# ft232.net
KiCad netlist of a schematic drawn in EAGLE
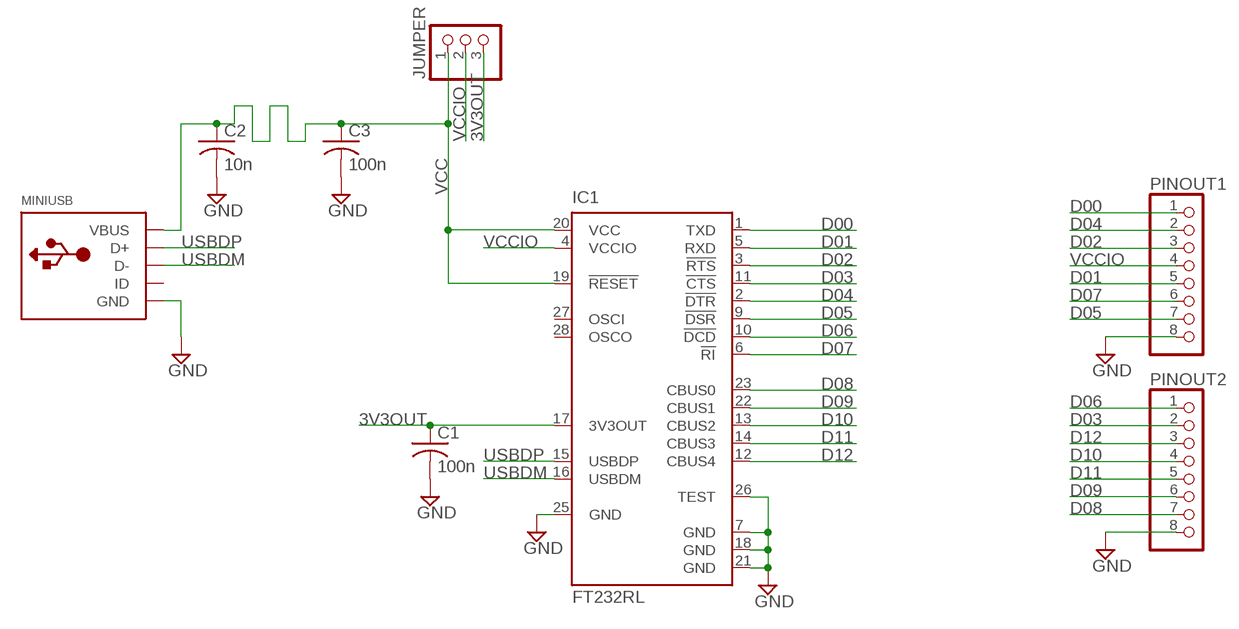
[diagram p0: schematic, sheet 1]

(export (version "E")
  (design (tool "Eeschema 10.0.6"))
  (components
    (comp (ref "C1")
      (value "100n")
      (footprint "eagle-import:C0805")
      (libsource (lib "eagle-import") (part "C-USC0805"))
    )
    (comp (ref "C2")
      (value "10n")
      (footprint "eagle-import:C0805")
      (libsource (lib "eagle-import") (part "C-USC0805"))
    )
    (comp (ref "C3")
      (value "100n")
      (footprint "eagle-import:C0805")
      (libsource (lib "eagle-import") (part "C-USC0805"))
    )
    (comp (ref "IC1")
      (value "FT232RL")
      (footprint "eagle-import:SSOP28")
      (libsource (lib "eagle-import") (part "FT232RL"))
    )
    (comp (ref "JUMPER")
      (value "PINHD-1X3CB")
      (footprint "eagle-import:1X03-CLEANBIG")
      (libsource (lib "eagle-import") (part "PINHD-1X3CB"))
    )
    (comp (ref "MINIUSB")
      (value "USBMINIB")
      (footprint "eagle-import:USB-MINIB")
      (libsource (lib "eagle-import") (part "USBMINIB"))
    )
    (comp (ref "PINOUT1")
      (value "PINHD-1X8")
      (footprint "eagle-import:1X08")
      (libsource (lib "eagle-import") (part "PINHD-1X8"))
    )
    (comp (ref "PINOUT2")
      (value "PINHD-1X8")
      (footprint "eagle-import:1X08")
      (libsource (lib "eagle-import") (part "PINHD-1X8"))
    )
  )
  (nets
    (net (code "1") (name "/3V3OUT") (class "Default")
      (node (ref "C1") (pin "1") (pinfunction "1_1") (pintype "passive"))
      (node (ref "IC1") (pin "17") (pinfunction "3V3OUT_17") (pintype "output"))
      (node (ref "JUMPER") (pin "3") (pinfunction "3_3") (pintype "passive"))
    )
    (net (code "2") (name "/D00") (class "Default")
      (node (ref "IC1") (pin "1") (pinfunction "TXD_1") (pintype "output"))
      (node (ref "PINOUT1") (pin "1") (pinfunction "1_1") (pintype "passive"))
    )
    (net (code "3") (name "/D01") (class "Default")
      (node (ref "IC1") (pin "5") (pinfunction "RXD_5") (pintype "input"))
      (node (ref "PINOUT1") (pin "5") (pinfunction "5_5") (pintype "passive"))
    )
    (net (code "4") (name "/D02") (class "Default")
      (node (ref "IC1") (pin "3") (pinfunction "~{RTS}_3") (pintype "output"))
      (node (ref "PINOUT1") (pin "3") (pinfunction "3_3") (pintype "passive"))
    )
    (net (code "5") (name "/D03") (class "Default")
      (node (ref "IC1") (pin "11") (pinfunction "~{CTS}_11") (pintype "input"))
      (node (ref "PINOUT2") (pin "2") (pinfunction "2_2") (pintype "passive"))
    )
    (net (code "6") (name "/D04") (class "Default")
      (node (ref "IC1") (pin "2") (pinfunction "~{DTR}_2") (pintype "output"))
      (node (ref "PINOUT1") (pin "2") (pinfunction "2_2") (pintype "passive"))
    )
    (net (code "7") (name "/D05") (class "Default")
      (node (ref "IC1") (pin "9") (pinfunction "~{DSR}_9") (pintype "input"))
      (node (ref "PINOUT1") (pin "7") (pinfunction "7_7") (pintype "passive"))
    )
    (net (code "8") (name "/D06") (class "Default")
      (node (ref "IC1") (pin "10") (pinfunction "~{DCD}_10") (pintype "input"))
      (node (ref "PINOUT2") (pin "1") (pinfunction "1_1") (pintype "passive"))
    )
    (net (code "9") (name "/D07") (class "Default")
      (node (ref "IC1") (pin "6") (pinfunction "~{RI}_6") (pintype "input"))
      (node (ref "PINOUT1") (pin "6") (pinfunction "6_6") (pintype "passive"))
    )
    (net (code "10") (name "/D08") (class "Default")
      (node (ref "IC1") (pin "23") (pinfunction "CBUS0_23") (pintype "bidirectional"))
      (node (ref "PINOUT2") (pin "7") (pinfunction "7_7") (pintype "passive"))
    )
    (net (code "11") (name "/D09") (class "Default")
      (node (ref "IC1") (pin "22") (pinfunction "CBUS1_22") (pintype "bidirectional"))
      (node (ref "PINOUT2") (pin "6") (pinfunction "6_6") (pintype "passive"))
    )
    (net (code "12") (name "/D10") (class "Default")
      (node (ref "IC1") (pin "13") (pinfunction "CBUS2_13") (pintype "bidirectional"))
      (node (ref "PINOUT2") (pin "4") (pinfunction "4_4") (pintype "passive"))
    )
    (net (code "13") (name "/D11") (class "Default")
      (node (ref "IC1") (pin "14") (pinfunction "CBUS3_14") (pintype "bidirectional"))
      (node (ref "PINOUT2") (pin "5") (pinfunction "5_5") (pintype "passive"))
    )
    (net (code "14") (name "/D12") (class "Default")
      (node (ref "IC1") (pin "12") (pinfunction "CBUS4_12") (pintype "bidirectional"))
      (node (ref "PINOUT2") (pin "3") (pinfunction "3_3") (pintype "passive"))
    )
    (net (code "15") (name "/USBDM") (class "Default")
      (node (ref "IC1") (pin "16") (pinfunction "USBDM_16") (pintype "bidirectional"))
      (node (ref "MINIUSB") (pin "D-") (pinfunction "D-_D-") (pintype "bidirectional"))
    )
    (net (code "16") (name "/USBDP") (class "Default")
      (node (ref "IC1") (pin "15") (pinfunction "USBDP_15") (pintype "bidirectional"))
      (node (ref "MINIUSB") (pin "D+") (pinfunction "D+_D+") (pintype "bidirectional"))
    )
    (net (code "17") (name "/VCC") (class "Default")
      (node (ref "C2") (pin "1") (pinfunction "1_1") (pintype "passive"))
      (node (ref "C3") (pin "1") (pinfunction "1_1") (pintype "passive"))
      (node (ref "IC1") (pin "19") (pinfunction "~{RESET}_19") (pintype "input"))
      (node (ref "IC1") (pin "20") (pinfunction "VCC_20") (pintype "power_in"))
      (node (ref "JUMPER") (pin "1") (pinfunction "1_1") (pintype "passive"))
      (node (ref "MINIUSB") (pin "VBUS") (pinfunction "VBUS_VBUS") (pintype "power_in"))
    )
    (net (code "18") (name "/VCCIO") (class "Default")
      (node (ref "IC1") (pin "4") (pinfunction "VCCIO_4") (pintype "power_in"))
      (node (ref "JUMPER") (pin "2") (pinfunction "2_2") (pintype "passive"))
      (node (ref "PINOUT1") (pin "4") (pinfunction "4_4") (pintype "passive"))
    )
    (net (code "19") (name "GND") (class "Default")
      (node (ref "C1") (pin "2") (pinfunction "2_2") (pintype "passive"))
      (node (ref "C2") (pin "2") (pinfunction "2_2") (pintype "passive"))
      (node (ref "C3") (pin "2") (pinfunction "2_2") (pintype "passive"))
      (node (ref "IC1") (pin "18") (pinfunction "GND_18") (pintype "power_in"))
      (node (ref "IC1") (pin "21") (pinfunction "GND_21") (pintype "power_in"))
      (node (ref "IC1") (pin "25") (pinfunction "GND_25") (pintype "power_in"))
      (node (ref "IC1") (pin "26") (pinfunction "TEST_26") (pintype "input"))
      (node (ref "IC1") (pin "7") (pinfunction "GND_7") (pintype "power_in"))
      (node (ref "MINIUSB") (pin "GND") (pinfunction "GND_GND") (pintype "power_in"))
      (node (ref "PINOUT1") (pin "8") (pinfunction "8_8") (pintype "passive"))
      (node (ref "PINOUT2") (pin "8") (pinfunction "8_8") (pintype "passive"))
    )
    (net (code "20") (name "unconnected-(IC1-OSCI-Pad27)") (class "Default")
      (node (ref "IC1") (pin "27") (pinfunction "OSCI_27") (pintype "input"))
    )
    (net (code "21") (name "unconnected-(IC1-OSCO-Pad28)") (class "Default")
      (node (ref "IC1") (pin "28") (pinfunction "OSCO_28") (pintype "output"))
    )
    (net (code "22") (name "unconnected-(MINIUSB-PadID)") (class "Default")
      (node (ref "MINIUSB") (pin "ID") (pinfunction "ID_ID") (pintype "bidirectional"))
    )
  )
)
